# DAC80508.net
KiCad netlist of a schematic drawn in Altium Designer
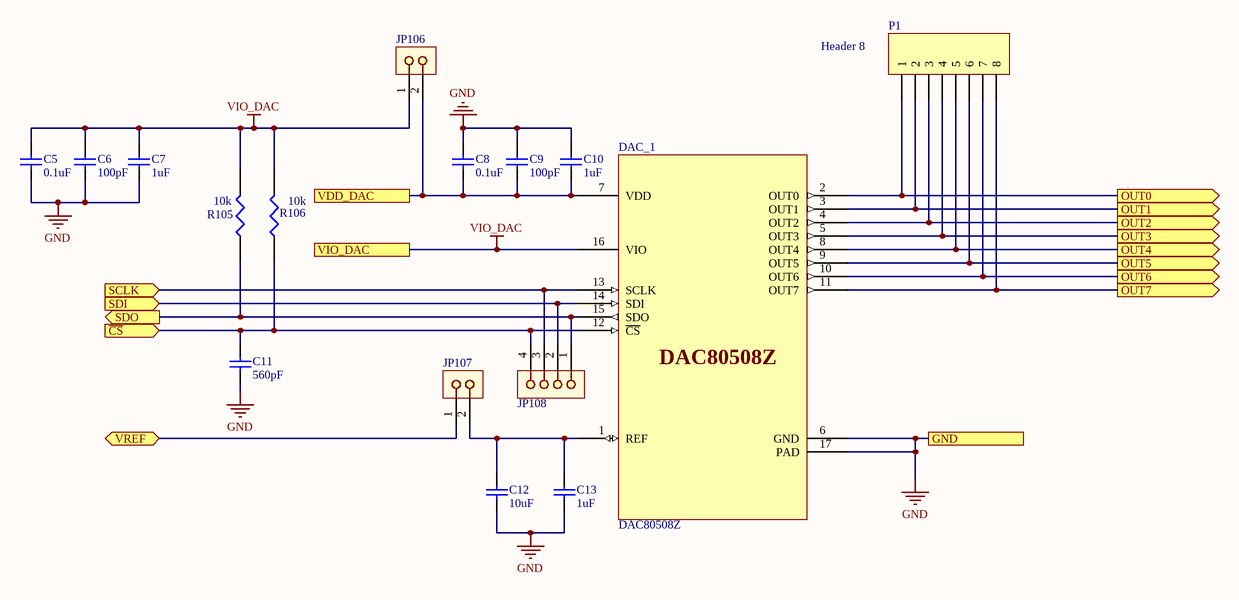
[diagram p0: DAC80508.SchDoc]

(export (version "E")
  (design (tool "Eeschema 10.0.6"))
  (components
    (comp (ref "C5")
      (value "0.1uF")
      (footprint "CLS_Library:C0805")
      (description "Cap 0.1uF")
      (fields
        (field (name "MANUFACTURER") "Taiyo Yuden")
        (field (name "MANUFACTURER PART NUMBER") "UMK212SD103KD-T")
      )
      (libsource (lib "Chip1_TestBoard") (part "Cap 0.1uF"))
    )
    (comp (ref "C6")
      (value "100pF")
      (footprint "CLS_Library:C0805")
      (description "Cap 100pF")
      (fields
        (field (name "MANUFACTURER") "Taiyo Yuden")
        (field (name "MANUFACTURER PART NUMBER") "UMK212SD103KD-T")
      )
      (libsource (lib "Chip1_TestBoard") (part "Cap 100pF"))
    )
    (comp (ref "C7")
      (value "1uF")
      (footprint "CLS_Library:C0805")
      (description "Cap 1uF")
      (fields
        (field (name "MANUFACTURER") "Taiyo Yuden")
        (field (name "MANUFACTURER PART NUMBER") "UMK212SD103KD-T")
      )
      (libsource (lib "Chip1_TestBoard") (part "Cap 1uF"))
    )
    (comp (ref "C8")
      (value "0.1uF")
      (footprint "CLS_Library:C0805")
      (description "Cap 0.1uF")
      (fields
        (field (name "MANUFACTURER") "Taiyo Yuden")
        (field (name "MANUFACTURER PART NUMBER") "UMK212SD103KD-T")
      )
      (libsource (lib "Chip1_TestBoard") (part "Cap 0.1uF"))
    )
    (comp (ref "C9")
      (value "100pF")
      (footprint "CLS_Library:C0805")
      (description "Cap 100pF")
      (fields
        (field (name "MANUFACTURER") "Taiyo Yuden")
        (field (name "MANUFACTURER PART NUMBER") "UMK212SD103KD-T")
      )
      (libsource (lib "Chip1_TestBoard") (part "Cap 100pF"))
    )
    (comp (ref "C10")
      (value "1uF")
      (footprint "CLS_Library:C0805")
      (description "Cap 1uF")
      (fields
        (field (name "MANUFACTURER") "Taiyo Yuden")
        (field (name "MANUFACTURER PART NUMBER") "UMK212SD103KD-T")
      )
      (libsource (lib "Chip1_TestBoard") (part "Cap 1uF"))
    )
    (comp (ref "C11")
      (value "560pF")
      (footprint "CLS_Library:C0805")
      (description "Cap 560pF")
      (fields
        (field (name "MANUFACTURER") "Taiyo Yuden")
        (field (name "MANUFACTURER PART NUMBER") "UMK212SD103KD-T")
      )
      (libsource (lib "Chip1_TestBoard") (part "Cap 560pF"))
    )
    (comp (ref "C12")
      (value "10uF")
      (footprint "CLS_Library:C0805")
      (description "Cap 10uF")
      (fields
        (field (name "MANUFACTURER") "Taiyo Yuden")
        (field (name "MANUFACTURER PART NUMBER") "UMK212SD103KD-T")
      )
      (libsource (lib "Chip1_TestBoard") (part "Cap 10uF"))
    )
    (comp (ref "C13")
      (value "1uF")
      (footprint "CLS_Library:C0805")
      (description "Cap 1uF")
      (fields
        (field (name "MANUFACTURER") "Taiyo Yuden")
        (field (name "MANUFACTURER PART NUMBER") "UMK212SD103KD-T")
      )
      (libsource (lib "Chip1_TestBoard") (part "Cap 1uF"))
    )
    (comp (ref "DAC_1")
      (value "DAC80508Z")
      (footprint "DAC80508Z")
      (description "Octal 16-bit Voltage DAC")
      (libsource (lib "Chip1_TestBoard") (part "DAC80508Z"))
    )
    (comp (ref "JP106")
      (value "01x02")
      (footprint "01x02_0.1in_th_straight_b_nom")
      (description "01X02 generic terminal connector")
      (libsource (lib "Chip1_TestBoard") (part "01x02"))
    )
    (comp (ref "JP107")
      (value "01x02")
      (footprint "01x02_0.1in_th_straight_b_nom")
      (description "01X02 generic terminal connector")
      (libsource (lib "Chip1_TestBoard") (part "01x02"))
    )
    (comp (ref "JP108")
      (value "01x04")
      (footprint "01x04_0.1in_th_straight_b_nom")
      (description "01X04 generic terminal connector")
      (libsource (lib "Chip1_TestBoard") (part "01x04"))
    )
    (comp (ref "P1")
      (value "Header 8")
      (footprint "HDR1X8")
      (description "Header, 8-Pin")
      (fields (field (name "PUBLISHER") "Altium Limited"))
      (libsource (lib "Miscellaneous Connectors") (part "Header 8"))
    )
    (comp (ref "R105") (value "10k") (footprint "R0805") (libsource (lib "Chip1_TestBoard") (part "Res 10k")))
    (comp (ref "R106") (value "10k") (footprint "R0805") (libsource (lib "Chip1_TestBoard") (part "Res 10k")))
  )
  (nets
    (net (code "1") (name "/OUT0") (class "Default")
      (node (ref "DAC_1") (pin "2") (pinfunction "OUT0_2") (pintype "output"))
      (node (ref "P1") (pin "1") (pinfunction "1_1") (pintype "passive"))
    )
    (net (code "2") (name "/OUT1") (class "Default")
      (node (ref "DAC_1") (pin "3") (pinfunction "OUT1_3") (pintype "output"))
      (node (ref "P1") (pin "2") (pinfunction "2_2") (pintype "passive"))
    )
    (net (code "3") (name "/OUT2") (class "Default")
      (node (ref "DAC_1") (pin "4") (pinfunction "OUT2_4") (pintype "output"))
      (node (ref "P1") (pin "3") (pinfunction "3_3") (pintype "passive"))
    )
    (net (code "4") (name "/OUT3") (class "Default")
      (node (ref "DAC_1") (pin "5") (pinfunction "OUT3_5") (pintype "output"))
      (node (ref "P1") (pin "4") (pinfunction "4_4") (pintype "passive"))
    )
    (net (code "5") (name "/OUT4") (class "Default")
      (node (ref "DAC_1") (pin "8") (pinfunction "OUT4_8") (pintype "output"))
      (node (ref "P1") (pin "5") (pinfunction "5_5") (pintype "passive"))
    )
    (net (code "6") (name "/OUT5") (class "Default")
      (node (ref "DAC_1") (pin "9") (pinfunction "OUT5_9") (pintype "output"))
      (node (ref "P1") (pin "6") (pinfunction "6_6") (pintype "passive"))
    )
    (net (code "7") (name "/OUT6") (class "Default")
      (node (ref "DAC_1") (pin "10") (pinfunction "OUT6_10") (pintype "output"))
      (node (ref "P1") (pin "7") (pinfunction "7_7") (pintype "passive"))
    )
    (net (code "8") (name "/OUT7") (class "Default")
      (node (ref "DAC_1") (pin "11") (pinfunction "OUT7_11") (pintype "output"))
      (node (ref "P1") (pin "8") (pinfunction "8_8") (pintype "passive"))
    )
    (net (code "9") (name "/SCLK") (class "Default")
      (node (ref "DAC_1") (pin "13") (pinfunction "SCLK_13") (pintype "input"))
      (node (ref "JP108") (pin "3") (pinfunction "3_3") (pintype "passive"))
    )
    (net (code "10") (name "/SDI") (class "Default")
      (node (ref "DAC_1") (pin "14") (pinfunction "SDI_14") (pintype "input"))
      (node (ref "JP108") (pin "2") (pinfunction "2_2") (pintype "passive"))
    )
    (net (code "11") (name "/SDO") (class "Default")
      (node (ref "DAC_1") (pin "15") (pinfunction "SDO_15") (pintype "output"))
      (node (ref "JP108") (pin "1") (pinfunction "1_1") (pintype "passive"))
      (node (ref "R105") (pin "1") (pinfunction "1_1") (pintype "passive"))
    )
    (net (code "12") (name "/VDD_DAC") (class "Default")
      (node (ref "C10") (pin "2") (pinfunction "2_2") (pintype "passive"))
      (node (ref "C8") (pin "1") (pinfunction "1_1") (pintype "passive"))
      (node (ref "C9") (pin "1") (pinfunction "1_1") (pintype "passive"))
      (node (ref "DAC_1") (pin "7") (pinfunction "VDD_7") (pintype "power_in"))
      (node (ref "JP106") (pin "2") (pinfunction "2_2") (pintype "passive"))
    )
    (net (code "13") (name "/VREF") (class "Default")
      (node (ref "JP107") (pin "1") (pinfunction "1_1") (pintype "passive"))
    )
    (net (code "14") (name "/~{CS}") (class "Default")
      (node (ref "C11") (pin "2") (pinfunction "2_2") (pintype "passive"))
      (node (ref "DAC_1") (pin "12") (pinfunction "~{CS}_12") (pintype "input"))
      (node (ref "JP108") (pin "4") (pinfunction "4_4") (pintype "passive"))
      (node (ref "R106") (pin "1") (pinfunction "1_1") (pintype "passive"))
    )
    (net (code "15") (name "GND") (class "Default")
      (node (ref "C10") (pin "1") (pinfunction "1_1") (pintype "passive"))
      (node (ref "C11") (pin "1") (pinfunction "1_1") (pintype "passive"))
      (node (ref "C12") (pin "1") (pinfunction "1_1") (pintype "passive"))
      (node (ref "C13") (pin "1") (pinfunction "1_1") (pintype "passive"))
      (node (ref "C5") (pin "1") (pinfunction "1_1") (pintype "passive"))
      (node (ref "C6") (pin "1") (pinfunction "1_1") (pintype "passive"))
      (node (ref "C7") (pin "2") (pinfunction "2_2") (pintype "passive"))
      (node (ref "C8") (pin "2") (pinfunction "2_2") (pintype "passive"))
      (node (ref "C9") (pin "2") (pinfunction "2_2") (pintype "passive"))
      (node (ref "DAC_1") (pin "17") (pinfunction "PAD_17") (pintype "power_in"))
      (node (ref "DAC_1") (pin "6") (pinfunction "GND_6") (pintype "power_in"))
    )
    (net (code "16") (name "Net-(DAC_1-REF)") (class "Default")
      (node (ref "C12") (pin "2") (pinfunction "2_2") (pintype "passive"))
      (node (ref "C13") (pin "2") (pinfunction "2_2") (pintype "passive"))
      (node (ref "DAC_1") (pin "1") (pinfunction "REF_1") (pintype "bidirectional"))
      (node (ref "JP107") (pin "2") (pinfunction "2_2") (pintype "passive"))
    )
    (net (code "17") (name "VIO_DAC") (class "Default")
      (node (ref "C5") (pin "2") (pinfunction "2_2") (pintype "passive"))
      (node (ref "C6") (pin "2") (pinfunction "2_2") (pintype "passive"))
      (node (ref "C7") (pin "1") (pinfunction "1_1") (pintype "passive"))
      (node (ref "DAC_1") (pin "16") (pinfunction "VIO_16") (pintype "power_in"))
      (node (ref "JP106") (pin "1") (pinfunction "1_1") (pintype "passive"))
      (node (ref "R105") (pin "2") (pinfunction "2_2") (pintype "passive"))
      (node (ref "R106") (pin "2") (pinfunction "2_2") (pintype "passive"))
    )
  )
)
